# Fleet-Monitor-Power.net
KiCad netlist of a schematic drawn in Altium Designer
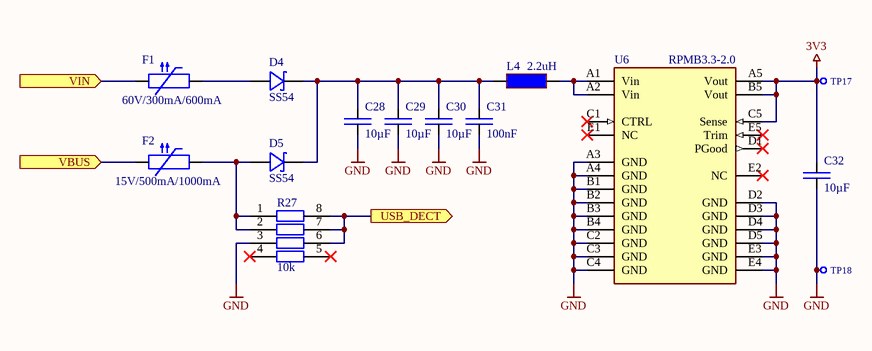
[diagram p0: Fleet-Monitor-Power.SchDoc]

(export (version "E")
  (design (tool "Eeschema 10.0.6"))
  (components
    (comp (ref "C28")
      (value "10µF")
      (footprint "SMD Keramikkondensator 0805")
      (description "SMD Ceramic Capacitor E6")
      (libsource (lib "Ceramic Capacitors-E6") (part "E6 - 10uF"))
    )
    (comp (ref "C29")
      (value "10µF")
      (footprint "SMD Keramikkondensator 0805")
      (description "SMD Ceramic Capacitor E6")
      (libsource (lib "Ceramic Capacitors-E6") (part "E6 - 10uF"))
    )
    (comp (ref "C30")
      (value "10µF")
      (footprint "SMD Keramikkondensator 0805")
      (description "SMD Ceramic Capacitor E6")
      (libsource (lib "Ceramic Capacitors-E6") (part "E6 - 10uF"))
    )
    (comp (ref "C31")
      (value "100nF")
      (footprint "SMD Keramikkondensator 0603")
      (description "SMD Ceramic Capacitor E6")
      (libsource (lib "Ceramic Capacitors-E6") (part "E6 - 100nF"))
    )
    (comp (ref "C32")
      (value "10µF")
      (footprint "SMD Keramikkondensator 0603")
      (description "SMD Ceramic Capacitor E6")
      (libsource (lib "Ceramic Capacitors-E6") (part "E6 - 10uF"))
    )
    (comp (ref "D4")
      (value "SS54")
      (footprint "SMD Diode DO-214-AC")
      (description "40V 5A 550mV @ 5A SMA(DO-214AC) Schottky Barrier Diodes (SBD) ROHS")
      (libsource (lib "Diodes") (part "SS54"))
    )
    (comp (ref "D5")
      (value "SS54")
      (footprint "SMD Diode DO-214-AC")
      (description "40V 5A 550mV @ 5A SMA(DO-214AC) Schottky Barrier Diodes (SBD) ROHS")
      (libsource (lib "Diodes") (part "SS54"))
    )
    (comp (ref "F1")
      (value "60V/300mA/600mA")
      (footprint "SMD PPTC-Fuse 1812")
      (description "60V 250mA 1s 1206 Resettable Fuses")
      (libsource (lib "Other") (part "JK-nSMD010"))
    )
    (comp (ref "F2")
      (value "15V/500mA/1000mA")
      (footprint "SMD PPTC-Fuse 1206")
      (description "30V 460mA 1206 Resettable Fuses")
      (libsource (lib "Other") (part "nSMD020-30V"))
    )
    (comp (ref "L4")
      (value "2.2uH")
      (footprint "SMD INDUCTOR/FERRITE 0805")
      (description "Ferrite Bead 2.2uH 2.6A / 142mOhm")
      (libsource (lib "Inductors") (part "TFM201610GHM-2R2MTAA"))
    )
    (comp (ref "R27")
      (value "10k")
      (footprint "SMD Widerstand Array 4-Fach 0603")
      (description "Isolated Resistor Array")
      (libsource (lib "Fleet-Monitor") (part "R-Array Single Quad E24 - 10k"))
    )
    (comp (ref "TP17")
      (value "X-TP")
      (footprint "SMD Testpunkt Ø1mm")
      (description "Testpunkt")
      (libsource (lib "VLD-Monitor_V1.0") (part "X-TP"))
    )
    (comp (ref "TP18")
      (value "X-TP")
      (footprint "SMD Testpunkt Ø1mm")
      (description "Testpunkt")
      (libsource (lib "VLD-Monitor_V1.0") (part "X-TP"))
    )
    (comp (ref "U6")
      (value "RPMB3.3-2.0")
      (footprint "SMD DCDC RPM 2.0")
      (description "Non-Isolated PoL Module DC DC Converter 1 Output 3.3V    2A 4V - 36V Input")
      (libsource (lib "Fleet-Monitor") (part "RPMB3.3-2.0"))
    )
  )
  (nets
    (net (code "1") (name "/USB_DECT") (class "Default")
      (node (ref "R27") (pin "6") (pinfunction "6_6") (pintype "passive"))
      (node (ref "R27") (pin "7") (pinfunction "7_7") (pintype "passive"))
      (node (ref "R27") (pin "8") (pinfunction "8_8") (pintype "passive"))
    )
    (net (code "2") (name "/VBUS") (class "Default")
      (node (ref "F2") (pin "1") (pinfunction "1_1") (pintype "passive"))
    )
    (net (code "3") (name "/VIN") (class "Default")
      (node (ref "F1") (pin "1") (pinfunction "1_1") (pintype "passive"))
    )
    (net (code "4") (name "3V3") (class "Default")
      (node (ref "C32") (pin "2") (pinfunction "2_2") (pintype "passive"))
      (node (ref "TP17") (pin "1") (pinfunction "1_1") (pintype "passive"))
      (node (ref "U6") (pin "A5") (pinfunction "Vout_A5") (pintype "passive"))
      (node (ref "U6") (pin "B5") (pinfunction "Vout_B5") (pintype "passive"))
      (node (ref "U6") (pin "C5") (pinfunction "Sense_C5") (pintype "input"))
    )
    (net (code "5") (name "GND") (class "Default")
      (node (ref "C28") (pin "1") (pinfunction "1_1") (pintype "passive"))
      (node (ref "C29") (pin "1") (pinfunction "1_1") (pintype "passive"))
      (node (ref "C30") (pin "1") (pinfunction "1_1") (pintype "passive"))
      (node (ref "C31") (pin "1") (pinfunction "1_1") (pintype "passive"))
      (node (ref "C32") (pin "1") (pinfunction "1_1") (pintype "passive"))
      (node (ref "R27") (pin "3") (pinfunction "3_3") (pintype "passive"))
      (node (ref "TP18") (pin "1") (pinfunction "1_1") (pintype "passive"))
      (node (ref "U6") (pin "A3") (pinfunction "GND_A3") (pintype "passive"))
      (node (ref "U6") (pin "A4") (pinfunction "GND_A4") (pintype "passive"))
      (node (ref "U6") (pin "B1") (pinfunction "GND_B1") (pintype "passive"))
      (node (ref "U6") (pin "B2") (pinfunction "GND_B2") (pintype "passive"))
      (node (ref "U6") (pin "B3") (pinfunction "GND_B3") (pintype "passive"))
      (node (ref "U6") (pin "B4") (pinfunction "GND_B4") (pintype "passive"))
      (node (ref "U6") (pin "C2") (pinfunction "GND_C2") (pintype "passive"))
      (node (ref "U6") (pin "C3") (pinfunction "GND_C3") (pintype "passive"))
      (node (ref "U6") (pin "C4") (pinfunction "GND_C4") (pintype "passive"))
      (node (ref "U6") (pin "D2") (pinfunction "GND_D2") (pintype "passive"))
      (node (ref "U6") (pin "D3") (pinfunction "GND_D3") (pintype "passive"))
      (node (ref "U6") (pin "D4") (pinfunction "GND_D4") (pintype "passive"))
      (node (ref "U6") (pin "D5") (pinfunction "GND_D5") (pintype "passive"))
      (node (ref "U6") (pin "E3") (pinfunction "GND_E3") (pintype "passive"))
      (node (ref "U6") (pin "E4") (pinfunction "GND_E4") (pintype "passive"))
    )
    (net (code "6") (name "Net-(C28-Pad2)") (class "Default")
      (node (ref "C28") (pin "2") (pinfunction "2_2") (pintype "passive"))
      (node (ref "C29") (pin "2") (pinfunction "2_2") (pintype "passive"))
      (node (ref "C30") (pin "2") (pinfunction "2_2") (pintype "passive"))
      (node (ref "C31") (pin "2") (pinfunction "2_2") (pintype "passive"))
      (node (ref "D4") (pin "K") (pinfunction "K_K") (pintype "passive"))
      (node (ref "D5") (pin "K") (pinfunction "K_K") (pintype "passive"))
      (node (ref "L4") (pin "1") (pinfunction "1_1") (pintype "passive"))
    )
    (net (code "7") (name "Net-(D4-PadA)") (class "Default")
      (node (ref "D4") (pin "A") (pinfunction "A_A") (pintype "passive"))
      (node (ref "F1") (pin "2") (pinfunction "2_2") (pintype "passive"))
    )
    (net (code "8") (name "Net-(D5-PadA)") (class "Default")
      (node (ref "D5") (pin "A") (pinfunction "A_A") (pintype "passive"))
      (node (ref "F2") (pin "2") (pinfunction "2_2") (pintype "passive"))
      (node (ref "R27") (pin "1") (pinfunction "1_1") (pintype "passive"))
      (node (ref "R27") (pin "2") (pinfunction "2_2") (pintype "passive"))
    )
    (net (code "9") (name "Net-(L4-Pad2)") (class "Default")
      (node (ref "L4") (pin "2") (pinfunction "2_2") (pintype "passive"))
      (node (ref "U6") (pin "A1") (pinfunction "Vin_A1") (pintype "passive"))
      (node (ref "U6") (pin "A2") (pinfunction "Vin_A2") (pintype "passive"))
    )
    (net (code "10") (name "unconnected-(R27-Pad4)") (class "Default")
      (node (ref "R27") (pin "4") (pinfunction "4_4") (pintype "passive+no_connect"))
    )
    (net (code "11") (name "unconnected-(R27-Pad5)") (class "Default")
      (node (ref "R27") (pin "5") (pinfunction "5_5") (pintype "passive+no_connect"))
    )
    (net (code "12") (name "unconnected-(U6-CTRL-PadC1)") (class "Default")
      (node (ref "U6") (pin "C1") (pinfunction "CTRL_C1") (pintype "input+no_connect"))
    )
    (net (code "13") (name "unconnected-(U6-NC-PadE1)") (class "Default")
      (node (ref "U6") (pin "E1") (pinfunction "NC_E1") (pintype "passive+no_connect"))
    )
    (net (code "14") (name "unconnected-(U6-NC-PadE2)") (class "Default")
      (node (ref "U6") (pin "E2") (pinfunction "NC_E2") (pintype "passive+no_connect"))
    )
    (net (code "15") (name "unconnected-(U6-PGood-PadD1)") (class "Default")
      (node (ref "U6") (pin "D1") (pinfunction "PGood_D1") (pintype "output+no_connect"))
    )
    (net (code "16") (name "unconnected-(U6-Trim-PadE5)") (class "Default")
      (node (ref "U6") (pin "E5") (pinfunction "Trim_E5") (pintype "input+no_connect"))
    )
  )
)
